# PP8_MMC.net
KiCad netlist of a schematic drawn in Altium Designer
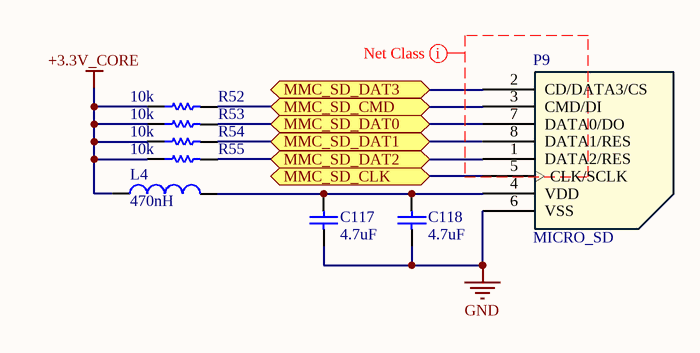
[diagram p0: PP8_MMC.SchDoc]

(export (version "E")
  (design (tool "Eeschema 10.0.6"))
  (components
    (comp (ref "C117")
      (value "4.7uF")
      (footprint "CAPC1608X08")
      (description "Capacitor")
      (fields (field (name "Comment") "Cap 4.7uF"))
      (libsource (lib "Michel") (part "Cap"))
    )
    (comp (ref "C118")
      (value "4.7uF")
      (footprint "CAPC1608X08")
      (description "Capacitor")
      (fields (field (name "Comment") "Cap 4.7uF"))
      (libsource (lib "Michel") (part "Cap"))
    )
    (comp (ref "L4")
      (value "470nH")
      (footprint "INDM1608X08N")
      (description "Inductor High Frequency")
      (libsource (lib "Miscellaneous Devices") (part "Inductor"))
    )
    (comp (ref "P9")
      (value "MICRO_SD")
      (footprint "WURTH ELEKTRONIK_693072010801")
      (description "Embase mémoire")
      (libsource (lib "Michel") (part "MicroSD"))
    )
    (comp (ref "R52")
      (value "10k")
      (footprint "RESC1608X05")
      (description "Resistor")
      (fields (field (name "Comment") "Res 10k"))
      (libsource (lib "Michel") (part "Res1"))
    )
    (comp (ref "R53")
      (value "10k")
      (footprint "RESC1608X05")
      (description "Resistor")
      (fields (field (name "Comment") "Res 10k"))
      (libsource (lib "Michel") (part "Res1"))
    )
    (comp (ref "R54")
      (value "10k")
      (footprint "RESC1608X05")
      (description "Resistor")
      (fields (field (name "Comment") "Res 10k"))
      (libsource (lib "Michel") (part "Res1"))
    )
    (comp (ref "R55")
      (value "10k")
      (footprint "RESC1608X05")
      (description "Resistor")
      (fields (field (name "Comment") "Res 10k"))
      (libsource (lib "Michel") (part "Res1"))
    )
  )
  (nets
    (net (code "1") (name "+3.3V_CORE") (class "Default")
      (node (ref "L4") (pin "1") (pinfunction "1_1") (pintype "passive"))
      (node (ref "R52") (pin "1") (pinfunction "1_1") (pintype "passive"))
      (node (ref "R53") (pin "1") (pinfunction "1_1") (pintype "passive"))
      (node (ref "R54") (pin "1") (pinfunction "1_1") (pintype "passive"))
      (node (ref "R55") (pin "1") (pinfunction "1_1") (pintype "passive"))
    )
    (net (code "2") (name "/MMC_SD_CLK") (class "Default")
      (node (ref "P9") (pin "5") (pinfunction "CLK/SCLK_5") (pintype "passive"))
    )
    (net (code "3") (name "/MMC_SD_CMD") (class "Default")
      (node (ref "P9") (pin "3") (pinfunction "CMD/DI_3") (pintype "passive"))
      (node (ref "R52") (pin "2") (pinfunction "2_2") (pintype "passive"))
    )
    (net (code "4") (name "/MMC_SD_DAT0") (class "Default")
      (node (ref "P9") (pin "7") (pinfunction "DATA0/DO_7") (pintype "passive"))
      (node (ref "R53") (pin "2") (pinfunction "2_2") (pintype "passive"))
    )
    (net (code "5") (name "/MMC_SD_DAT1") (class "Default")
      (node (ref "P9") (pin "8") (pinfunction "DATA1/RES_8") (pintype "passive"))
      (node (ref "R54") (pin "2") (pinfunction "2_2") (pintype "passive"))
    )
    (net (code "6") (name "/MMC_SD_DAT2") (class "Default")
      (node (ref "P9") (pin "1") (pinfunction "DATA2/RES_1") (pintype "passive"))
      (node (ref "R55") (pin "2") (pinfunction "2_2") (pintype "passive"))
    )
    (net (code "7") (name "/MMC_SD_DAT3") (class "Default")
      (node (ref "P9") (pin "2") (pinfunction "CD/DATA3/CS_2") (pintype "passive"))
    )
    (net (code "8") (name "GND") (class "Default")
      (node (ref "C117") (pin "1") (pinfunction "1_1") (pintype "passive"))
      (node (ref "C118") (pin "2") (pinfunction "2_2") (pintype "passive"))
      (node (ref "P9") (pin "6") (pinfunction "VSS_6") (pintype "power_in"))
    )
    (net (code "9") (name "Net-(P9-VDD)") (class "Default")
      (node (ref "C117") (pin "2") (pinfunction "2_2") (pintype "passive"))
      (node (ref "C118") (pin "1") (pinfunction "1_1") (pintype "passive"))
      (node (ref "L4") (pin "2") (pinfunction "2_2") (pintype "passive"))
      (node (ref "P9") (pin "4") (pinfunction "VDD_4") (pintype "power_in"))
    )
  )
)
